# 12_Periphs.net
KiCad netlist of a schematic drawn in Altium Designer
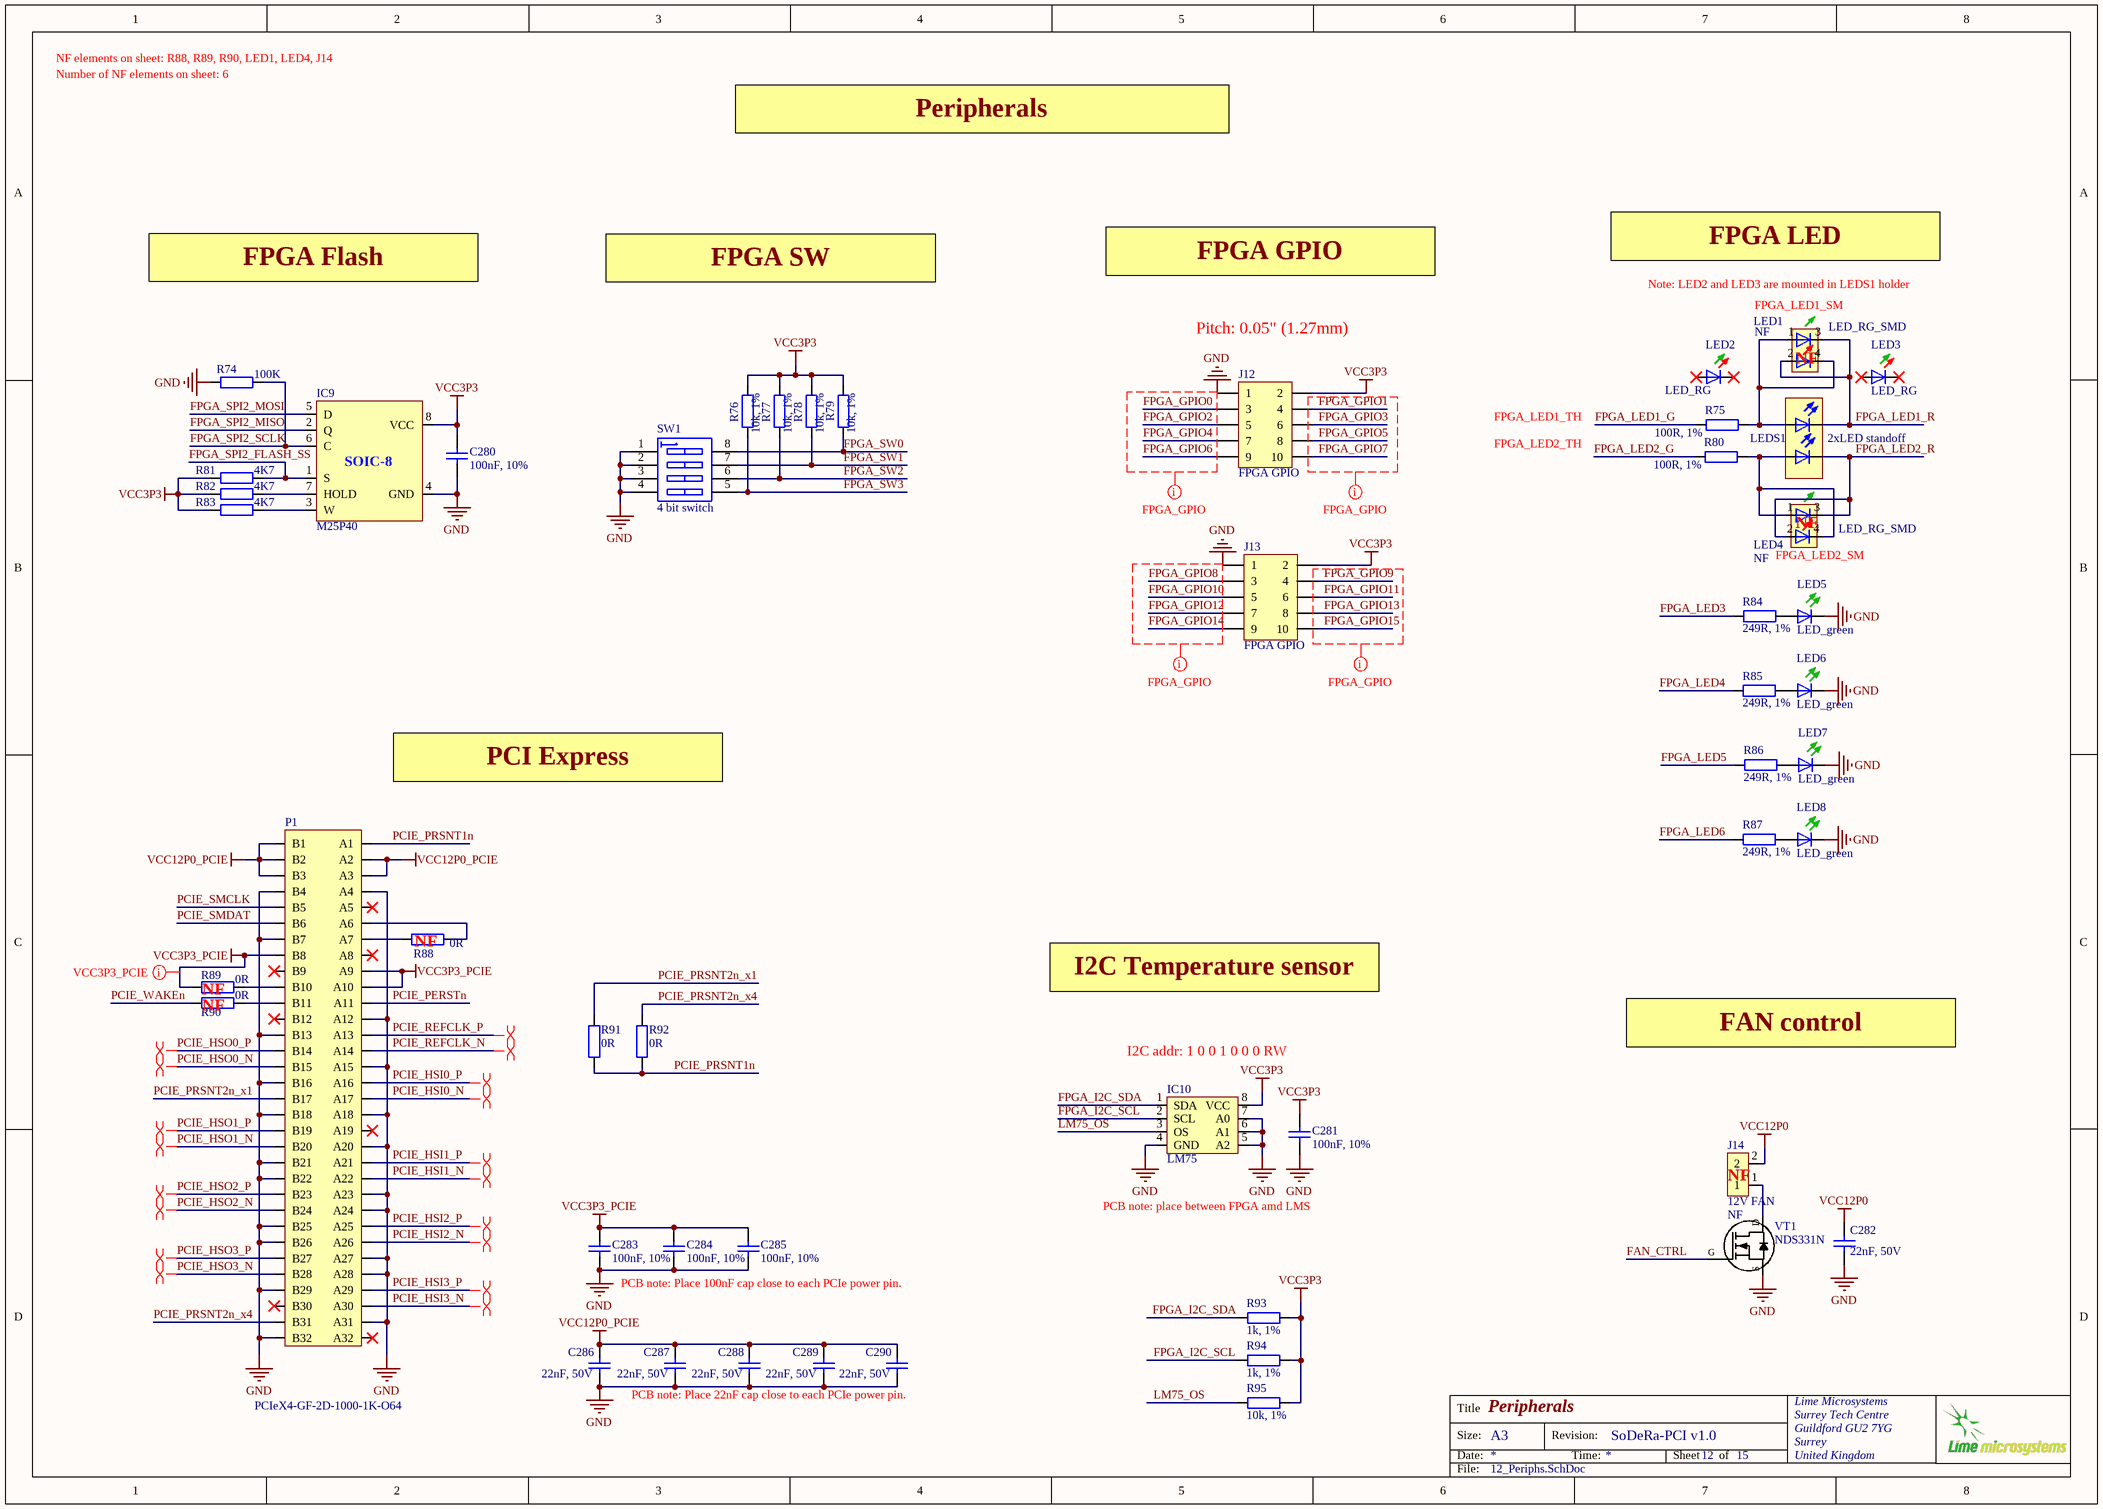
[diagram p0: 12_Periphs.SchDoc]

(export (version "E")
  (design (tool "Eeschema 10.0.6"))
  (components
    (comp (ref "C280")
      (value "100nF, 10%")
      (footprint "LimeMicroAltiumLib_pcbLib:CAP0402")
      (fields
        (field (name "TOLERANCE") "10 %")
        (field (name "MANUFACTURER") "Murata")
        (field (name "MANUFACTURER PART NUMBER") "GRM155R71C104KA88D")
      )
      (libsource (lib "LimeFPGAboard_schLib") (part "Cap_0603"))
    )
    (comp (ref "C281")
      (value "100nF, 10%")
      (footprint "LimeMicroAltiumLib_pcbLib:CAP0402")
      (fields
        (field (name "TOLERANCE") "10 %")
        (field (name "MANUFACTURER") "Murata")
        (field (name "MANUFACTURER PART NUMBER") "GRM155R71C104KA88D")
      )
      (libsource (lib "LimeFPGAboard_schLib") (part "Cap_0603"))
    )
    (comp (ref "C282")
      (value "22nF, 50V")
      (footprint "LimeMicroAltiumLib_pcbLib:CAP0402")
      (fields (field (name "TOLERANCE") "±10%") (field (name "MANUFACTURER") "Kemet"))
      (libsource (lib "LimeMicroAltiumLib_schLib") (part "Cap_0402"))
    )
    (comp (ref "C283")
      (value "100nF, 10%")
      (footprint "LimeMicroAltiumLib_pcbLib:CAP0402")
      (fields (field (name "TOLERANCE") "10 %") (field (name "MANUFACTURER") "Murata"))
      (libsource (lib "LimeFPGAboard_schLib") (part "Cap_0603"))
    )
    (comp (ref "C284")
      (value "100nF, 10%")
      (footprint "LimeMicroAltiumLib_pcbLib:CAP0402")
      (fields (field (name "TOLERANCE") "10 %") (field (name "MANUFACTURER") "Murata"))
      (libsource (lib "LimeFPGAboard_schLib") (part "Cap_0603"))
    )
    (comp (ref "C285")
      (value "100nF, 10%")
      (footprint "LimeMicroAltiumLib_pcbLib:CAP0402")
      (fields (field (name "TOLERANCE") "10 %") (field (name "MANUFACTURER") "Murata"))
      (libsource (lib "LimeFPGAboard_schLib") (part "Cap_0603"))
    )
    (comp (ref "C286")
      (value "22nF, 50V")
      (footprint "LimeMicroAltiumLib_pcbLib:CAP0402")
      (fields (field (name "TOLERANCE") "±10%") (field (name "MANUFACTURER") "Kemet"))
      (libsource (lib "LimeMicroAltiumLib_schLib") (part "Cap_0402"))
    )
    (comp (ref "C287")
      (value "22nF, 50V")
      (footprint "LimeMicroAltiumLib_pcbLib:CAP0402")
      (fields (field (name "TOLERANCE") "±10%") (field (name "MANUFACTURER") "Kemet"))
      (libsource (lib "LimeMicroAltiumLib_schLib") (part "Cap_0402"))
    )
    (comp (ref "C288")
      (value "22nF, 50V")
      (footprint "LimeMicroAltiumLib_pcbLib:CAP0402")
      (fields (field (name "TOLERANCE") "±10%") (field (name "MANUFACTURER") "Kemet"))
      (libsource (lib "LimeMicroAltiumLib_schLib") (part "Cap_0402"))
    )
    (comp (ref "C289")
      (value "22nF, 50V")
      (footprint "LimeMicroAltiumLib_pcbLib:CAP0402")
      (fields (field (name "TOLERANCE") "±10%") (field (name "MANUFACTURER") "Kemet"))
      (libsource (lib "LimeMicroAltiumLib_schLib") (part "Cap_0402"))
    )
    (comp (ref "C290")
      (value "22nF, 50V")
      (footprint "LimeMicroAltiumLib_pcbLib:CAP0402")
      (fields (field (name "TOLERANCE") "±10%") (field (name "MANUFACTURER") "Kemet"))
      (libsource (lib "LimeMicroAltiumLib_schLib") (part "Cap_0402"))
    )
    (comp (ref "IC9")
      (value "M25P40")
      (footprint "LimeMicroAltiumLib_pcbLib:M25P40-VMN6TPB_SO8N")
      (fields (field (name "MANUFACTURER") "Micron Technology Inc"))
      (libsource (lib "LimeFPGAboard_schLib") (part "M25P40"))
    )
    (comp (ref "IC10")
      (value "LM75")
      (footprint "LimeMicroAltiumLib_pcbLib:HWSON8_LM75")
      (fields
        (field (name "MANUFACTURER") "NXP Semiconductors")
        (field (name "MANUFACTURER PART NUMBER") "LM75BTP,147")
      )
      (libsource (lib "LimeMicroAltiumLib_schLib") (part "LM75"))
    )
    (comp (ref "J12")
      (value "FPGA GPIO")
      (footprint "LimeMicroAltiumLib_pcbLib:SWD_10_pin")
      (description "Header, 5-Pin, Dual row")
      (fields (field (name "MANUFACTURER") "Harwin Inc"))
      (libsource (lib "LimeMicroAltiumLib_schLib") (part "Header 5X2_SWD"))
    )
    (comp (ref "J13")
      (value "FPGA GPIO")
      (footprint "LimeMicroAltiumLib_pcbLib:SWD_10_pin")
      (description "Header, 5-Pin, Dual row")
      (fields (field (name "MANUFACTURER") "Harwin Inc"))
      (libsource (lib "LimeMicroAltiumLib_schLib") (part "Header 5X2_SWD"))
    )
    (comp (ref "J14")
      (value "12V FAN")
      (footprint "LimeMicroAltiumLib_pcbLib:HDR_1x2")
      (fields (field (name "ASSEMBLY INFO") "NF"))
      (libsource (lib "LimeFPGAboard_schLib") (part "Jumper"))
    )
    (comp (ref "LED1")
      (value "LED_RG_SMD")
      (footprint "LimeMicroAltiumLib_pcbLib:LED-2x0603")
      (fields (field (name "MANUFACTURER") "Avago Technologies US Inc.") (field (name "ASSEMBLY INFO") "NF"))
      (libsource (lib "LimeMicroAltiumLib_schLib") (part "LED_green_red_SMD"))
    )
    (comp (ref "LED2")
      (value "LED_RG")
      (fields (field (name "MANUFACTURER") "Visual Communications Company - VCC"))
      (libsource (lib "LimeMicroAltiumLib_schLib") (part "LED_green_red"))
    )
    (comp (ref "LED3")
      (value "LED_RG")
      (fields (field (name "MANUFACTURER") "Visual Communications Company - VCC"))
      (libsource (lib "LimeMicroAltiumLib_schLib") (part "LED_green_red"))
    )
    (comp (ref "LED4")
      (value "LED_RG_SMD")
      (footprint "LimeMicroAltiumLib_pcbLib:LED-2x0603")
      (fields (field (name "MANUFACTURER") "Avago Technologies US Inc.") (field (name "ASSEMBLY INFO") "NF"))
      (libsource (lib "LimeMicroAltiumLib_schLib") (part "LED_green_red_SMD"))
    )
    (comp (ref "LED5")
      (value "LED_green")
      (footprint "LimeMicroAltiumLib_pcbLib:LED-0603-GREEN")
      (libsource (lib "LimeFPGAboard_schLib") (part "LED_green"))
    )
    (comp (ref "LED6")
      (value "LED_green")
      (footprint "LimeMicroAltiumLib_pcbLib:LED-0603-GREEN")
      (libsource (lib "LimeFPGAboard_schLib") (part "LED_green"))
    )
    (comp (ref "LED7")
      (value "LED_green")
      (footprint "LimeMicroAltiumLib_pcbLib:LED-0603-GREEN")
      (libsource (lib "LimeFPGAboard_schLib") (part "LED_green"))
    )
    (comp (ref "LED8")
      (value "LED_green")
      (footprint "LimeMicroAltiumLib_pcbLib:LED-0603-GREEN")
      (libsource (lib "LimeFPGAboard_schLib") (part "LED_green"))
    )
    (comp (ref "LEDS1")
      (value "2xLED standoff")
      (footprint "LimeMicroAltiumLib_pcbLib:LED_STANDOFF_H-201C")
      (fields (field (name "MANUFACTURER") "Bivar Inc."))
      (libsource (lib "LimeMicroAltiumLib_schLib") (part "LEDx2_STANDOFF"))
    )
    (comp (ref "P1")
      (value "PCIeX4-GF-2D-1000-1K-O64")
      (footprint "LimeMicroAltiumLib_pcbLib:PCIeX4-GF-2D-1000-1K-O64")
      (libsource (lib "LimeMicroAltiumLib_schLib") (part "PCIeX4-GF-2D-1000-1K-O64"))
    )
    (comp (ref "R74")
      (value "100K")
      (footprint "LimeMicroAltiumLib_pcbLib:RES0402")
      (fields
        (field (name "TOLERANCE") "±5%")
        (field (name "MANUFACTURER") "Panasonic Electronic Components")
      )
      (libsource (lib "LimeFPGAboard_schLib") (part "Res_0402"))
    )
    (comp (ref "R75")
      (value "100R, 1%")
      (footprint "LimeMicroAltiumLib_pcbLib:RES0402")
      (fields (field (name "TOLERANCE") "±1%") (field (name "MANUFACTURER") "Stackpole Electronics Inc"))
      (libsource (lib "LimeMicroAltiumLib_schLib") (part "Res_0402"))
    )
    (comp (ref "R76")
      (value "10k, 1%")
      (footprint "LimeMicroAltiumLib_pcbLib:RES0402")
      (fields (field (name "MANUFACTURER") "Yageo") (field (name "TOLERANCE") "±1%"))
      (libsource (lib "LimeMicroAltiumLib_schLib") (part "Res_0402"))
    )
    (comp (ref "R77")
      (value "10k, 1%")
      (footprint "LimeMicroAltiumLib_pcbLib:RES0402")
      (fields (field (name "MANUFACTURER") "Yageo") (field (name "TOLERANCE") "±1%"))
      (libsource (lib "LimeMicroAltiumLib_schLib") (part "Res_0402"))
    )
    (comp (ref "R78")
      (value "10k, 1%")
      (footprint "LimeMicroAltiumLib_pcbLib:RES0402")
      (fields (field (name "MANUFACTURER") "Yageo") (field (name "TOLERANCE") "±1%"))
      (libsource (lib "LimeMicroAltiumLib_schLib") (part "Res_0402"))
    )
    (comp (ref "R79")
      (value "10k, 1%")
      (footprint "LimeMicroAltiumLib_pcbLib:RES0402")
      (fields (field (name "MANUFACTURER") "Yageo") (field (name "TOLERANCE") "±1%"))
      (libsource (lib "LimeMicroAltiumLib_schLib") (part "Res_0402"))
    )
    (comp (ref "R80")
      (value "100R, 1%")
      (footprint "LimeMicroAltiumLib_pcbLib:RES0402")
      (fields (field (name "TOLERANCE") "±1%") (field (name "MANUFACTURER") "Stackpole Electronics Inc"))
      (libsource (lib "LimeMicroAltiumLib_schLib") (part "Res_0402"))
    )
    (comp (ref "R81")
      (value "4K7")
      (footprint "LimeMicroAltiumLib_pcbLib:RES0402")
      (fields (field (name "TOLERANCE") "±5%"))
      (libsource (lib "LimeFPGAboard_schLib") (part "Res_0402"))
    )
    (comp (ref "R82")
      (value "4K7")
      (footprint "LimeMicroAltiumLib_pcbLib:RES0402")
      (fields (field (name "TOLERANCE") "±5%"))
      (libsource (lib "LimeFPGAboard_schLib") (part "Res_0402"))
    )
    (comp (ref "R83")
      (value "4K7")
      (footprint "LimeMicroAltiumLib_pcbLib:RES0402")
      (fields (field (name "TOLERANCE") "±5%"))
      (libsource (lib "LimeFPGAboard_schLib") (part "Res_0402"))
    )
    (comp (ref "R84")
      (value "249R, 1%")
      (footprint "LimeMicroAltiumLib_pcbLib:RES0402")
      (fields (field (name "MANUFACTURER") "Stackpole Electronics Inc") (field (name "TOLERANCE") "±1%"))
      (libsource (lib "LimeMicroAltiumLib_schLib") (part "Res_0402"))
    )
    (comp (ref "R85")
      (value "249R, 1%")
      (footprint "LimeMicroAltiumLib_pcbLib:RES0402")
      (fields (field (name "MANUFACTURER") "Stackpole Electronics Inc") (field (name "TOLERANCE") "±1%"))
      (libsource (lib "LimeMicroAltiumLib_schLib") (part "Res_0402"))
    )
    (comp (ref "R86")
      (value "249R, 1%")
      (footprint "LimeMicroAltiumLib_pcbLib:RES0402")
      (fields (field (name "MANUFACTURER") "Stackpole Electronics Inc") (field (name "TOLERANCE") "±1%"))
      (libsource (lib "LimeMicroAltiumLib_schLib") (part "Res_0402"))
    )
    (comp (ref "R87")
      (value "249R, 1%")
      (footprint "LimeMicroAltiumLib_pcbLib:RES0402")
      (fields (field (name "MANUFACTURER") "Stackpole Electronics Inc") (field (name "TOLERANCE") "±1%"))
      (libsource (lib "LimeMicroAltiumLib_schLib") (part "Res_0402"))
    )
    (comp (ref "R88")
      (value "0R")
      (footprint "LimeMicroAltiumLib_pcbLib:RES0402")
      (fields (field (name "MANUFACTURER") "Yageo"))
      (libsource (lib "LimeFPGAboard_schLib") (part "Res_0402"))
    )
    (comp (ref "R89")
      (value "0R")
      (footprint "LimeMicroAltiumLib_pcbLib:RES0402")
      (fields (field (name "MANUFACTURER") "Yageo"))
      (libsource (lib "LimeFPGAboard_schLib") (part "Res_0402"))
    )
    (comp (ref "R90")
      (value "0R")
      (footprint "LimeMicroAltiumLib_pcbLib:RES0402")
      (fields (field (name "MANUFACTURER") "Yageo"))
      (libsource (lib "LimeFPGAboard_schLib") (part "Res_0402"))
    )
    (comp (ref "R91")
      (value "0R")
      (footprint "LimeMicroAltiumLib_pcbLib:RES0402")
      (fields (field (name "MANUFACTURER") "Yageo"))
      (libsource (lib "LimeFPGAboard_schLib") (part "Res_0402"))
    )
    (comp (ref "R92")
      (value "0R")
      (footprint "LimeMicroAltiumLib_pcbLib:RES0402")
      (fields (field (name "MANUFACTURER") "Yageo"))
      (libsource (lib "LimeFPGAboard_schLib") (part "Res_0402"))
    )
    (comp (ref "R93")
      (value "1k, 1%")
      (footprint "LimeMicroAltiumLib_pcbLib:RES0402")
      (fields (field (name "MANUFACTURER") "Stackpole Electronics Inc") (field (name "TOLERANCE") "±1%"))
      (libsource (lib "LimeMicroAltiumLib_schLib") (part "Res_0402"))
    )
    (comp (ref "R94")
      (value "1k, 1%")
      (footprint "LimeMicroAltiumLib_pcbLib:RES0402")
      (fields (field (name "MANUFACTURER") "Stackpole Electronics Inc") (field (name "TOLERANCE") "±1%"))
      (libsource (lib "LimeMicroAltiumLib_schLib") (part "Res_0402"))
    )
    (comp (ref "R95")
      (value "10k, 1%")
      (footprint "LimeMicroAltiumLib_pcbLib:RES0402")
      (fields (field (name "MANUFACTURER") "Yageo") (field (name "TOLERANCE") "±1%"))
      (libsource (lib "LimeMicroAltiumLib_schLib") (part "Res_0402"))
    )
    (comp (ref "SW1")
      (value "4 bit switch")
      (footprint "LimeMicroAltiumLib_pcbLib:SW_4WAY_SMD_1P27")
      (fields (field (name "MANUFACTURER") "Omron Electronics Inc-EMC Div"))
      (libsource (lib "LimeMicroAltiumLib_schLib") (part "SW_SM_4bit"))
    )
    (comp (ref "VT1")
      (value "NDS331N")
      (footprint "LimeMicroAltiumLib_pcbLib:SOT23-3")
      (libsource (lib "LimeFPGAboard_schLib") (part "NDS331N"))
    )
  )
  (nets
    (net (code "1") (name "/FAN_CTRL") (class "Default")
      (node (ref "VT1") (pin "G") (pinfunction "G_G") (pintype "passive"))
    )
    (net (code "2") (name "/FPGA_GPIO0") (class "Default")
      (node (ref "J12") (pin "3") (pinfunction "3_3") (pintype "passive"))
    )
    (net (code "3") (name "/FPGA_GPIO1") (class "Default")
      (node (ref "J12") (pin "4") (pinfunction "4_4") (pintype "passive"))
    )
    (net (code "4") (name "/FPGA_GPIO2") (class "Default")
      (node (ref "J12") (pin "5") (pinfunction "5_5") (pintype "passive"))
    )
    (net (code "5") (name "/FPGA_GPIO3") (class "Default")
      (node (ref "J12") (pin "6") (pinfunction "6_6") (pintype "passive"))
    )
    (net (code "6") (name "/FPGA_GPIO4") (class "Default")
      (node (ref "J12") (pin "7") (pinfunction "7_7") (pintype "passive"))
    )
    (net (code "7") (name "/FPGA_GPIO5") (class "Default")
      (node (ref "J12") (pin "8") (pinfunction "8_8") (pintype "passive"))
    )
    (net (code "8") (name "/FPGA_GPIO6") (class "Default")
      (node (ref "J12") (pin "9") (pinfunction "9_9") (pintype "passive"))
    )
    (net (code "9") (name "/FPGA_GPIO7") (class "Default")
      (node (ref "J12") (pin "10") (pinfunction "10_10") (pintype "passive"))
    )
    (net (code "10") (name "/FPGA_GPIO8") (class "Default")
      (node (ref "J13") (pin "3") (pinfunction "3_3") (pintype "passive"))
    )
    (net (code "11") (name "/FPGA_GPIO9") (class "Default")
      (node (ref "J13") (pin "4") (pinfunction "4_4") (pintype "passive"))
    )
    (net (code "12") (name "/FPGA_GPIO10") (class "Default")
      (node (ref "J13") (pin "5") (pinfunction "5_5") (pintype "passive"))
    )
    (net (code "13") (name "/FPGA_GPIO11") (class "Default")
      (node (ref "J13") (pin "6") (pinfunction "6_6") (pintype "passive"))
    )
    (net (code "14") (name "/FPGA_GPIO12") (class "Default")
      (node (ref "J13") (pin "7") (pinfunction "7_7") (pintype "passive"))
    )
    (net (code "15") (name "/FPGA_GPIO13") (class "Default")
      (node (ref "J13") (pin "8") (pinfunction "8_8") (pintype "passive"))
    )
    (net (code "16") (name "/FPGA_GPIO14") (class "Default")
      (node (ref "J13") (pin "9") (pinfunction "9_9") (pintype "passive"))
    )
    (net (code "17") (name "/FPGA_GPIO15") (class "Default")
      (node (ref "J13") (pin "10") (pinfunction "10_10") (pintype "passive"))
    )
    (net (code "18") (name "/FPGA_I2C_SCL") (class "Default")
      (node (ref "IC10") (pin "2") (pinfunction "SCL_2") (pintype "passive"))
      (node (ref "R94") (pin "2") (pinfunction "2_2") (pintype "passive"))
    )
    (net (code "19") (name "/FPGA_I2C_SDA") (class "Default")
      (node (ref "IC10") (pin "1") (pinfunction "SDA_1") (pintype "passive"))
      (node (ref "R93") (pin "2") (pinfunction "2_2") (pintype "passive"))
    )
    (net (code "20") (name "/FPGA_LED1_G") (class "Default")
      (node (ref "R75") (pin "1") (pinfunction "1_1") (pintype "passive"))
    )
    (net (code "21") (name "/FPGA_LED1_R") (class "Default")
      (node (ref "LED1") (pin "2") (pinfunction "2_2") (pintype "power_in"))
      (node (ref "LED1") (pin "3") (pinfunction "3_3") (pintype "power_in"))
      (node (ref "LEDS1") (pin "K1") (pinfunction "C_K1") (pintype "power_in"))
    )
    (net (code "22") (name "/FPGA_LED2_G") (class "Default")
      (node (ref "R80") (pin "1") (pinfunction "1_1") (pintype "passive"))
    )
    (net (code "23") (name "/FPGA_LED2_R") (class "Default")
      (node (ref "LED4") (pin "2") (pinfunction "2_2") (pintype "power_in"))
      (node (ref "LED4") (pin "3") (pinfunction "3_3") (pintype "power_in"))
      (node (ref "LEDS1") (pin "K2") (pinfunction "C_K2") (pintype "power_in"))
    )
    (net (code "24") (name "/FPGA_LED3") (class "Default")
      (node (ref "R84") (pin "1") (pinfunction "1_1") (pintype "passive"))
    )
    (net (code "25") (name "/FPGA_LED4") (class "Default")
      (node (ref "R85") (pin "1") (pinfunction "1_1") (pintype "passive"))
    )
    (net (code "26") (name "/FPGA_LED5") (class "Default")
      (node (ref "R86") (pin "1") (pinfunction "1_1") (pintype "passive"))
    )
    (net (code "27") (name "/FPGA_LED6") (class "Default")
      (node (ref "R87") (pin "1") (pinfunction "1_1") (pintype "passive"))
    )
    (net (code "28") (name "/FPGA_SPI2_FLASH_SS") (class "Default")
      (node (ref "IC9") (pin "1") (pinfunction "S_1") (pintype "passive"))
      (node (ref "R81") (pin "2") (pinfunction "2_2") (pintype "passive"))
    )
    (net (code "29") (name "/FPGA_SPI2_MISO") (class "Default")
      (node (ref "IC9") (pin "2") (pinfunction "Q_2") (pintype "passive"))
    )
    (net (code "30") (name "/FPGA_SPI2_MOSI") (class "Default")
      (node (ref "IC9") (pin "5") (pinfunction "D_5") (pintype "passive"))
    )
    (net (code "31") (name "/FPGA_SPI2_SCLK") (class "Default")
      (node (ref "IC9") (pin "6") (pinfunction "C_6") (pintype "passive"))
      (node (ref "R74") (pin "2") (pinfunction "2_2") (pintype "passive"))
    )
    (net (code "32") (name "/FPGA_SW0") (class "Default")
      (node (ref "R79") (pin "2") (pinfunction "2_2") (pintype "passive"))
      (node (ref "SW1") (pin "8") (pinfunction "B1_8") (pintype "passive"))
    )
    (net (code "33") (name "/FPGA_SW1") (class "Default")
      (node (ref "R78") (pin "2") (pinfunction "2_2") (pintype "passive"))
      (node (ref "SW1") (pin "7") (pinfunction "B2_7") (pintype "passive"))
    )
    (net (code "34") (name "/FPGA_SW2") (class "Default")
      (node (ref "R77") (pin "2") (pinfunction "2_2") (pintype "passive"))
      (node (ref "SW1") (pin "6") (pinfunction "B3_6") (pintype "passive"))
    )
    (net (code "35") (name "/FPGA_SW3") (class "Default")
      (node (ref "R76") (pin "2") (pinfunction "2_2") (pintype "passive"))
      (node (ref "SW1") (pin "5") (pinfunction "B4_5") (pintype "passive"))
    )
    (net (code "36") (name "/LM75_OS") (class "Default")
      (node (ref "IC10") (pin "3") (pinfunction "OS_3") (pintype "passive"))
      (node (ref "R95") (pin "2") (pinfunction "2_2") (pintype "passive"))
    )
    (net (code "37") (name "/PCIE_HSI0_N") (class "Default")
      (node (ref "P1") (pin "A17") (pinfunction "A17_A17") (pintype "passive"))
    )
    (net (code "38") (name "/PCIE_HSI0_P") (class "Default")
      (node (ref "P1") (pin "A16") (pinfunction "A16_A16") (pintype "passive"))
    )
    (net (code "39") (name "/PCIE_HSI1_N") (class "Default")
      (node (ref "P1") (pin "A22") (pinfunction "A22_A22") (pintype "passive"))
    )
    (net (code "40") (name "/PCIE_HSI1_P") (class "Default")
      (node (ref "P1") (pin "A21") (pinfunction "A21_A21") (pintype "passive"))
    )
    (net (code "41") (name "/PCIE_HSI2_N") (class "Default")
      (node (ref "P1") (pin "A26") (pinfunction "A26_A26") (pintype "passive"))
    )
    (net (code "42") (name "/PCIE_HSI2_P") (class "Default")
      (node (ref "P1") (pin "A25") (pinfunction "A25_A25") (pintype "passive"))
    )
    (net (code "43") (name "/PCIE_HSI3_N") (class "Default")
      (node (ref "P1") (pin "A30") (pinfunction "A30_A30") (pintype "passive"))
    )
    (net (code "44") (name "/PCIE_HSI3_P") (class "Default")
      (node (ref "P1") (pin "A29") (pinfunction "A29_A29") (pintype "passive"))
    )
    (net (code "45") (name "/PCIE_HSO0_N") (class "Default")
      (node (ref "P1") (pin "B15") (pinfunction "B15_B15") (pintype "passive"))
    )
    (net (code "46") (name "/PCIE_HSO0_P") (class "Default")
      (node (ref "P1") (pin "B14") (pinfunction "B14_B14") (pintype "passive"))
    )
    (net (code "47") (name "/PCIE_HSO1_N") (class "Default")
      (node (ref "P1") (pin "B20") (pinfunction "B20_B20") (pintype "passive"))
    )
    (net (code "48") (name "/PCIE_HSO1_P") (class "Default")
      (node (ref "P1") (pin "B19") (pinfunction "B19_B19") (pintype "passive"))
    )
    (net (code "49") (name "/PCIE_HSO2_N") (class "Default")
      (node (ref "P1") (pin "B24") (pinfunction "B24_B24") (pintype "passive"))
    )
    (net (code "50") (name "/PCIE_HSO2_P") (class "Default")
      (node (ref "P1") (pin "B23") (pinfunction "B23_B23") (pintype "passive"))
    )
    (net (code "51") (name "/PCIE_HSO3_N") (class "Default")
      (node (ref "P1") (pin "B28") (pinfunction "B28_B28") (pintype "passive"))
    )
    (net (code "52") (name "/PCIE_HSO3_P") (class "Default")
      (node (ref "P1") (pin "B27") (pinfunction "B27_B27") (pintype "passive"))
    )
    (net (code "53") (name "/PCIE_PERSTn") (class "Default")
      (node (ref "P1") (pin "A11") (pinfunction "A11_A11") (pintype "passive"))
    )
    (net (code "54") (name "/PCIE_PRSNT1n") (class "Default")
      (node (ref "P1") (pin "A1") (pinfunction "A1_A1") (pintype "passive"))
      (node (ref "R91") (pin "1") (pinfunction "1_1") (pintype "passive"))
      (node (ref "R92") (pin "1") (pinfunction "1_1") (pintype "passive"))
    )
    (net (code "55") (name "/PCIE_PRSNT2n_x1") (class "Default")
      (node (ref "P1") (pin "B17") (pinfunction "B17_B17") (pintype "passive"))
      (node (ref "R91") (pin "2") (pinfunction "2_2") (pintype "passive"))
    )
    (net (code "56") (name "/PCIE_PRSNT2n_x4") (class "Default")
      (node (ref "P1") (pin "B31") (pinfunction "B31_B31") (pintype "passive"))
      (node (ref "R92") (pin "2") (pinfunction "2_2") (pintype "passive"))
    )
    (net (code "57") (name "/PCIE_REFCLK_N") (class "Default")
      (node (ref "P1") (pin "A14") (pinfunction "A14_A14") (pintype "passive"))
    )
    (net (code "58") (name "/PCIE_REFCLK_P") (class "Default")
      (node (ref "P1") (pin "A13") (pinfunction "A13_A13") (pintype "passive"))
    )
    (net (code "59") (name "/PCIE_SMCLK") (class "Default")
      (node (ref "P1") (pin "B5") (pinfunction "B5_B5") (pintype "passive"))
    )
    (net (code "60") (name "/PCIE_SMDAT") (class "Default")
      (node (ref "P1") (pin "B6") (pinfunction "B6_B6") (pintype "passive"))
    )
    (net (code "61") (name "/PCIE_WAKEn") (class "Default")
      (node (ref "R90") (pin "1") (pinfunction "1_1") (pintype "passive"))
    )
    (net (code "62") (name "GND") (class "Default")
      (node (ref "C280") (pin "2") (pinfunction "2_2") (pintype "passive"))
      (node (ref "C281") (pin "2") (pinfunction "2_2") (pintype "passive"))
      (node (ref "C282") (pin "2") (pinfunction "2_2") (pintype "passive"))
      (node (ref "C283") (pin "2") (pinfunction "2_2") (pintype "passive"))
      (node (ref "C284") (pin "2") (pinfunction "2_2") (pintype "passive"))
      (node (ref "C285") (pin "2") (pinfunction "2_2") (pintype "passive"))
      (node (ref "C286") (pin "2") (pinfunction "2_2") (pintype "passive"))
      (node (ref "C287") (pin "2") (pinfunction "2_2") (pintype "passive"))
      (node (ref "C288") (pin "2") (pinfunction "2_2") (pintype "passive"))
      (node (ref "C289") (pin "2") (pinfunction "2_2") (pintype "passive"))
      (node (ref "C290") (pin "2") (pinfunction "2_2") (pintype "passive"))
      (node (ref "IC10") (pin "4") (pinfunction "GND_4") (pintype "passive"))
      (node (ref "IC10") (pin "5") (pinfunction "A2_5") (pintype "passive"))
      (node (ref "IC10") (pin "6") (pinfunction "A1_6") (pintype "passive"))
      (node (ref "IC10") (pin "7") (pinfunction "A0_7") (pintype "passive"))
      (node (ref "IC9") (pin "4") (pinfunction "GND_4") (pintype "passive"))
      (node (ref "J12") (pin "1") (pinfunction "1_1") (pintype "passive"))
      (node (ref "J13") (pin "1") (pinfunction "1_1") (pintype "passive"))
      (node (ref "LED5") (pin "K") (pinfunction "C_K") (pintype "power_in"))
      (node (ref "LED6") (pin "K") (pinfunction "C_K") (pintype "power_in"))
      (node (ref "LED7") (pin "K") (pinfunction "C_K") (pintype "power_in"))
      (node (ref "LED8") (pin "K") (pinfunction "C_K") (pintype "power_in"))
      (node (ref "P1") (pin "A12") (pinfunction "A12_A12") (pintype "passive"))
      (node (ref "P1") (pin "A15") (pinfunction "A15_A15") (pintype "passive"))
      (node (ref "P1") (pin "A18") (pinfunction "A18_A18") (pintype "passive"))
      (node (ref "P1") (pin "A20") (pinfunction "A20_A20") (pintype "passive"))
      (node (ref "P1") (pin "A23") (pinfunction "A23_A23") (pintype "passive"))
      (node (ref "P1") (pin "A24") (pinfunction "A24_A24") (pintype "passive"))
      (node (ref "P1") (pin "A27") (pinfunction "A27_A27") (pintype "passive"))
      (node (ref "P1") (pin "A28") (pinfunction "A28_A28") (pintype "passive"))
      (node (ref "P1") (pin "A31") (pinfunction "A31_A31") (pintype "passive"))
      (node (ref "P1") (pin "A4") (pinfunction "A4_A4") (pintype "passive"))
      (node (ref "P1") (pin "B13") (pinfunction "B13_B13") (pintype "passive"))
      (node (ref "P1") (pin "B16") (pinfunction "B16_B16") (pintype "passive"))
      (node (ref "P1") (pin "B18") (pinfunction "B18_B18") (pintype "passive"))
      (node (ref "P1") (pin "B21") (pinfunction "B21_B21") (pintype "passive"))
      (node (ref "P1") (pin "B22") (pinfunction "B22_B22") (pintype "passive"))
      (node (ref "P1") (pin "B25") (pinfunction "B25_B25") (pintype "passive"))
      (node (ref "P1") (pin "B26") (pinfunction "B26_B26") (pintype "passive"))
      (node (ref "P1") (pin "B29") (pinfunction "B29_B29") (pintype "passive"))
      (node (ref "P1") (pin "B32") (pinfunction "B32_B32") (pintype "passive"))
      (node (ref "P1") (pin "B4") (pinfunction "B4_B4") (pintype "passive"))
      (node (ref "P1") (pin "B7") (pinfunction "B7_B7") (pintype "passive"))
      (node (ref "R74") (pin "1") (pinfunction "1_1") (pintype "passive"))
      (node (ref "SW1") (pin "1") (pinfunction "A1_1") (pintype "passive"))
      (node (ref "SW1") (pin "2") (pinfunction "A2_2") (pintype "passive"))
      (node (ref "SW1") (pin "3") (pinfunction "A3_3") (pintype "passive"))
      (node (ref "SW1") (pin "4") (pinfunction "A4_4") (pintype "passive"))
      (node (ref "VT1") (pin "S") (pinfunction "S_S") (pintype "passive"))
    )
    (net (code "63") (name "Net-(IC9-HOLD)") (class "Default")
      (node (ref "IC9") (pin "7") (pinfunction "HOLD_7") (pintype "passive"))
      (node (ref "R82") (pin "2") (pinfunction "2_2") (pintype "passive"))
    )
    (net (code "64") (name "Net-(IC9-W)") (class "Default")
      (node (ref "IC9") (pin "3") (pinfunction "W_3") (pintype "passive"))
      (node (ref "R83") (pin "2") (pinfunction "2_2") (pintype "passive"))
    )
    (net (code "65") (name "Net-(J14-Pad1)") (class "Default")
      (node (ref "J14") (pin "1") (pinfunction "1_1") (pintype "passive"))
      (node (ref "VT1") (pin "D") (pinfunction "D_D") (pintype "passive"))
    )
    (net (code "66") (name "Net-(LED1-Pad1)") (class "Default")
      (node (ref "LED1") (pin "1") (pinfunction "1_1") (pintype "power_in"))
      (node (ref "LED1") (pin "4") (pinfunction "4_4") (pintype "power_in"))
      (node (ref "LEDS1") (pin "A1") (pinfunction "A_A1") (pintype "power_in"))
      (node (ref "R75") (pin "2") (pinfunction "2_2") (pintype "passive"))
    )
    (net (code "67") (name "Net-(LED4-Pad1)") (class "Default")
      (node (ref "LED4") (pin "1") (pinfunction "1_1") (pintype "power_in"))
      (node (ref "LED4") (pin "4") (pinfunction "4_4") (pintype "power_in"))
      (node (ref "LEDS1") (pin "A2") (pinfunction "A_A2") (pintype "power_in"))
      (node (ref "R80") (pin "2") (pinfunction "2_2") (pintype "passive"))
    )
    (net (code "68") (name "Net-(LED5-PadA)") (class "Default")
      (node (ref "LED5") (pin "A") (pinfunction "A_A") (pintype "power_in"))
      (node (ref "R84") (pin "2") (pinfunction "2_2") (pintype "passive"))
    )
    (net (code "69") (name "Net-(LED6-PadA)") (class "Default")
      (node (ref "LED6") (pin "A") (pinfunction "A_A") (pintype "power_in"))
      (node (ref "R85") (pin "2") (pinfunction "2_2") (pintype "passive"))
    )
    (net (code "70") (name "Net-(LED7-PadA)") (class "Default")
      (node (ref "LED7") (pin "A") (pinfunction "A_A") (pintype "power_in"))
      (node (ref "R86") (pin "2") (pinfunction "2_2") (pintype "passive"))
    )
    (net (code "71") (name "Net-(LED8-PadA)") (class "Default")
      (node (ref "LED8") (pin "A") (pinfunction "A_A") (pintype "power_in"))
      (node (ref "R87") (pin "2") (pinfunction "2_2") (pintype "passive"))
    )
    (net (code "72") (name "Net-(P1-PadA6)") (class "Default")
      (node (ref "P1") (pin "A6") (pinfunction "A6_A6") (pintype "passive"))
      (node (ref "R88") (pin "2") (pinfunction "2_2") (pintype "passive"))
    )
    (net (code "73") (name "Net-(P1-PadA7)") (class "Default")
      (node (ref "P1") (pin "A7") (pinfunction "A7_A7") (pintype "passive"))
      (node (ref "R88") (pin "1") (pinfunction "1_1") (pintype "passive"))
    )
    (net (code "74") (name "Net-(P1-PadB10)") (class "Default")
      (node (ref "P1") (pin "B10") (pinfunction "B10_B10") (pintype "passive"))
      (node (ref "R89") (pin "2") (pinfunction "2_2") (pintype "passive"))
    )
    (net (code "75") (name "Net-(P1-PadB11)") (class "Default")
      (node (ref "P1") (pin "B11") (pinfunction "B11_B11") (pintype "passive"))
      (node (ref "R90") (pin "2") (pinfunction "2_2") (pintype "passive"))
    )
    (net (code "76") (name "VCC3P3") (class "Default")
      (node (ref "C280") (pin "1") (pinfunction "1_1") (pintype "passive"))
      (node (ref "C281") (pin "1") (pinfunction "1_1") (pintype "passive"))
      (node (ref "IC10") (pin "8") (pinfunction "VCC_8") (pintype "passive"))
      (node (ref "IC9") (pin "8") (pinfunction "VCC_8") (pintype "passive"))
      (node (ref "J12") (pin "2") (pinfunction "2_2") (pintype "passive"))
      (node (ref "J13") (pin "2") (pinfunction "2_2") (pintype "passive"))
      (node (ref "R76") (pin "1") (pinfunction "1_1") (pintype "passive"))
      (node (ref "R77") (pin "1") (pinfunction "1_1") (pintype "passive"))
      (node (ref "R78") (pin "1") (pinfunction "1_1") (pintype "passive"))
      (node (ref "R79") (pin "1") (pinfunction "1_1") (pintype "passive"))
      (node (ref "R81") (pin "1") (pinfunction "1_1") (pintype "passive"))
      (node (ref "R82") (pin "1") (pinfunction "1_1") (pintype "passive"))
      (node (ref "R83") (pin "1") (pinfunction "1_1") (pintype "passive"))
      (node (ref "R93") (pin "1") (pinfunction "1_1") (pintype "passive"))
      (node (ref "R94") (pin "1") (pinfunction "1_1") (pintype "passive"))
      (node (ref "R95") (pin "1") (pinfunction "1_1") (pintype "passive"))
    )
    (net (code "77") (name "VCC3P3_PCIE") (class "Default")
      (node (ref "C283") (pin "1") (pinfunction "1_1") (pintype "passive"))
      (node (ref "C284") (pin "1") (pinfunction "1_1") (pintype "passive"))
      (node (ref "C285") (pin "1") (pinfunction "1_1") (pintype "passive"))
      (node (ref "P1") (pin "A10") (pinfunction "A10_A10") (pintype "passive"))
      (node (ref "P1") (pin "A9") (pinfunction "A9_A9") (pintype "passive"))
      (node (ref "P1") (pin "B8") (pinfunction "B8_B8") (pintype "passive"))
      (node (ref "R89") (pin "1") (pinfunction "1_1") (pintype "passive"))
    )
    (net (code "78") (name "VCC12P0") (class "Default")
      (node (ref "C282") (pin "1") (pinfunction "1_1") (pintype "passive"))
      (node (ref "J14") (pin "2") (pinfunction "2_2") (pintype "passive"))
    )
    (net (code "79") (name "VCC12P0_PCIE") (class "Default")
      (node (ref "C286") (pin "1") (pinfunction "1_1") (pintype "passive"))
      (node (ref "C287") (pin "1") (pinfunction "1_1") (pintype "passive"))
      (node (ref "C288") (pin "1") (pinfunction "1_1") (pintype "passive"))
      (node (ref "C289") (pin "1") (pinfunction "1_1") (pintype "passive"))
      (node (ref "C290") (pin "1") (pinfunction "1_1") (pintype "passive"))
      (node (ref "P1") (pin "A2") (pinfunction "A2_A2") (pintype "passive"))
      (node (ref "P1") (pin "A3") (pinfunction "A3_A3") (pintype "passive"))
      (node (ref "P1") (pin "B1") (pinfunction "B1_B1") (pintype "passive"))
      (node (ref "P1") (pin "B2") (pinfunction "B2_B2") (pintype "passive"))
      (node (ref "P1") (pin "B3") (pinfunction "B3_B3") (pintype "passive"))
    )
    (net (code "80") (name "unconnected-(LED2-C-PadK)") (class "Default")
      (node (ref "LED2") (pin "K") (pinfunction "C_K") (pintype "power_in+no_connect"))
    )
    (net (code "81") (name "unconnected-(LED2-PadA)") (class "Default")
      (node (ref "LED2") (pin "A") (pinfunction "A_A") (pintype "power_in+no_connect"))
    )
    (net (code "82") (name "unconnected-(LED3-C-PadK)") (class "Default")
      (node (ref "LED3") (pin "K") (pinfunction "C_K") (pintype "power_in+no_connect"))
    )
    (net (code "83") (name "unconnected-(LED3-PadA)") (class "Default")
      (node (ref "LED3") (pin "A") (pinfunction "A_A") (pintype "power_in+no_connect"))
    )
    (net (code "84") (name "unconnected-(P1-PadA5)") (class "Default")
      (node (ref "P1") (pin "A5") (pinfunction "A5_A5") (pintype "passive+no_connect"))
    )
    (net (code "85") (name "unconnected-(P1-PadA8)") (class "Default")
      (node (ref "P1") (pin "A8") (pinfunction "A8_A8") (pintype "passive+no_connect"))
    )
    (net (code "86") (name "unconnected-(P1-PadA19)") (class "Default")
      (node (ref "P1") (pin "A19") (pinfunction "A19_A19") (pintype "passive+no_connect"))
    )
    (net (code "87") (name "unconnected-(P1-PadA32)") (class "Default")
      (node (ref "P1") (pin "A32") (pinfunction "A32_A32") (pintype "passive+no_connect"))
    )
    (net (code "88") (name "unconnected-(P1-PadB9)") (class "Default")
      (node (ref "P1") (pin "B9") (pinfunction "B9_B9") (pintype "passive+no_connect"))
    )
    (net (code "89") (name "unconnected-(P1-PadB12)") (class "Default")
      (node (ref "P1") (pin "B12") (pinfunction "B12_B12") (pintype "passive+no_connect"))
    )
    (net (code "90") (name "unconnected-(P1-PadB30)") (class "Default")
      (node (ref "P1") (pin "B30") (pinfunction "B30_B30") (pintype "passive+no_connect"))
    )
  )
)
